# 03_iMX_8X_PMIC.net
KiCad netlist of a schematic drawn in Altium Designer
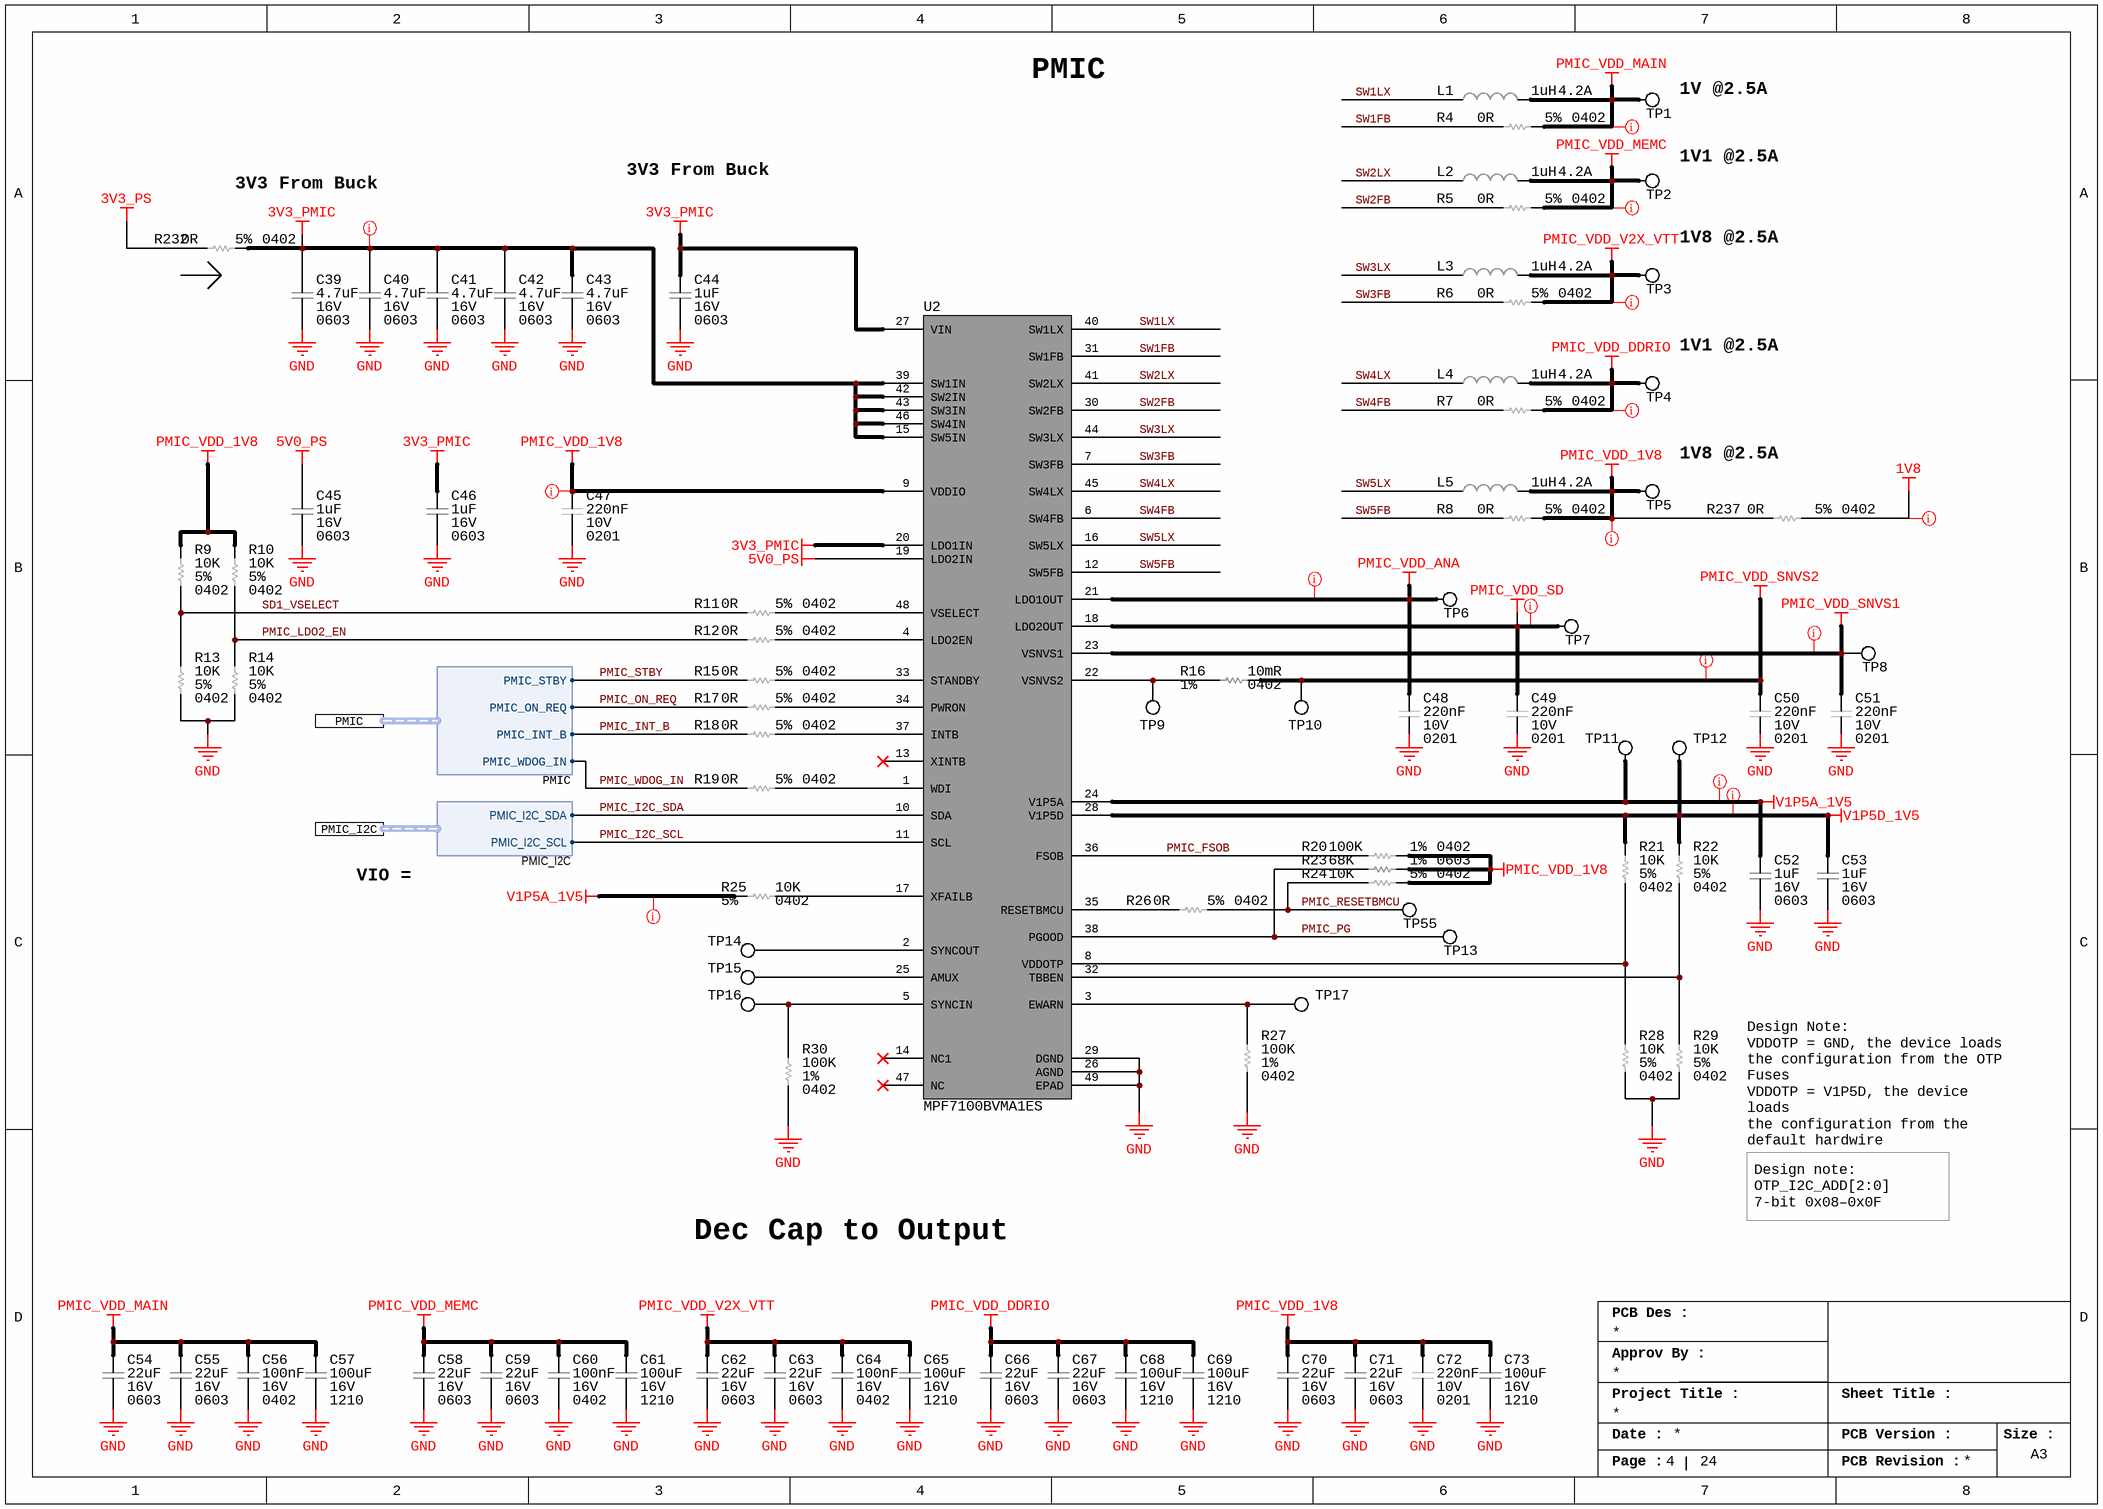
[diagram p0: 03_iMX 8X_PMIC.SchDoc]

(export (version "E")
  (design (tool "Eeschema 10.0.6"))
  (components
    (comp (ref "C39")
      (value "CL10A475KO8NNNC")
      (footprint "CAP_0603_CAPC1608X08N")
      (description "CAP CER 4.7UF 16V X5R 0603")
      (fields
        (field (name "MANUFACTURER") "Samsung")
        (field (name "TOLERANCE") "10%")
        (field (name "VOLTAGE") "16V")
        (field (name "CAPACITANCE") "4.7uF")
        (field (name "CASE/PACKAGE") "0603")
      )
      (libsource (lib "Electronic Devices_LIB") (part "CAP_4.7UF_16V_X5R_0603"))
    )
    (comp (ref "C40")
      (value "CL10A475KO8NNNC")
      (footprint "CAP_0603_CAPC1608X08N")
      (description "CAP CER 4.7UF 16V X5R 0603")
      (fields
        (field (name "MANUFACTURER") "Samsung")
        (field (name "TOLERANCE") "10%")
        (field (name "VOLTAGE") "16V")
        (field (name "CAPACITANCE") "4.7uF")
        (field (name "CASE/PACKAGE") "0603")
      )
      (libsource (lib "Electronic Devices_LIB") (part "CAP_4.7UF_16V_X5R_0603"))
    )
    (comp (ref "C41")
      (value "CL10A475KO8NNNC")
      (footprint "CAP_0603_CAPC1608X08N")
      (description "CAP CER 4.7UF 16V X5R 0603")
      (fields
        (field (name "MANUFACTURER") "Samsung")
        (field (name "TOLERANCE") "10%")
        (field (name "VOLTAGE") "16V")
        (field (name "CAPACITANCE") "4.7uF")
        (field (name "CASE/PACKAGE") "0603")
      )
      (libsource (lib "Electronic Devices_LIB") (part "CAP_4.7UF_16V_X5R_0603"))
    )
    (comp (ref "C42")
      (value "CL10A475KO8NNNC")
      (footprint "CAP_0603_CAPC1608X08N")
      (description "CAP CER 4.7UF 16V X5R 0603")
      (fields
        (field (name "MANUFACTURER") "Samsung")
        (field (name "TOLERANCE") "10%")
        (field (name "VOLTAGE") "16V")
        (field (name "CAPACITANCE") "4.7uF")
        (field (name "CASE/PACKAGE") "0603")
      )
      (libsource (lib "Electronic Devices_LIB") (part "CAP_4.7UF_16V_X5R_0603"))
    )
    (comp (ref "C43")
      (value "CL10A475KO8NNNC")
      (footprint "CAP_0603_CAPC1608X08N")
      (description "CAP CER 4.7UF 16V X5R 0603")
      (fields
        (field (name "MANUFACTURER") "Samsung")
        (field (name "TOLERANCE") "10%")
        (field (name "VOLTAGE") "16V")
        (field (name "CAPACITANCE") "4.7uF")
        (field (name "CASE/PACKAGE") "0603")
      )
      (libsource (lib "Electronic Devices_LIB") (part "CAP_4.7UF_16V_X5R_0603"))
    )
    (comp (ref "C44")
      (value "CL10A105KO8NNNC")
      (footprint "CAP_0603_CAPC1608X08N")
      (description "CAP CER 1UF 16V X5R 0603")
      (fields
        (field (name "MANUFACTURER") "Samsung")
        (field (name "TOLERANCE") "10%")
        (field (name "VOLTAGE RATING") "16V")
        (field (name "CAPACITANCE") "1uF")
        (field (name "CASE/PACKAGE") "0603")
      )
      (libsource (lib "Electronic Devices_LIB") (part "CAP_1UF_16V_X5R_0603"))
    )
    (comp (ref "C45")
      (value "CL10A105KO8NNNC")
      (footprint "CAP_0603_CAPC1608X08N")
      (description "CAP CER 1UF 16V X5R 0603")
      (fields
        (field (name "MANUFACTURER") "Samsung")
        (field (name "TOLERANCE") "10%")
        (field (name "VOLTAGE RATING") "16V")
        (field (name "CAPACITANCE") "1uF")
        (field (name "CASE/PACKAGE") "0603")
      )
      (libsource (lib "Electronic Devices_LIB") (part "CAP_1UF_16V_X5R_0603"))
    )
    (comp (ref "C46")
      (value "CL10A105KO8NNNC")
      (footprint "CAP_0603_CAPC1608X08N")
      (description "CAP CER 1UF 16V X5R 0603")
      (fields
        (field (name "MANUFACTURER") "Samsung")
        (field (name "TOLERANCE") "10%")
        (field (name "VOLTAGE RATING") "16V")
        (field (name "CAPACITANCE") "1uF")
        (field (name "CASE/PACKAGE") "0603")
      )
      (libsource (lib "Electronic Devices_LIB") (part "CAP_1UF_16V_X5R_0603"))
    )
    (comp (ref "C47")
      (value "LMK063BJ224MP-F")
      (footprint "CAP_0201_CAPC0603X03N")
      (description "Multilayer Ceramic Capacitors (High dielectric type), 10V, 0.22 uF, ± 20 %, 0201, X5R, RoHS")
      (fields
        (field (name "MANUFACTURER") "Taiyo Yuden")
        (field (name "TOLERANCE") "20%")
        (field (name "VOLTAGE RATING (DC)") "10V")
        (field (name "CAPACITANCE") "220nF")
        (field (name "CASE/PACKAGE") "0201")
      )
      (libsource (lib "Electronic Devices_LIB") (part "CAP_0.22UF_10V_X5R_0201"))
    )
    (comp (ref "C48")
      (value "LMK063BJ224MP-F")
      (footprint "CAP_0201_CAPC0603X03N")
      (description "Multilayer Ceramic Capacitors (High dielectric type), 10V, 0.22 uF, ± 20 %, 0201, X5R, RoHS")
      (fields
        (field (name "MANUFACTURER") "Taiyo Yuden")
        (field (name "TOLERANCE") "20%")
        (field (name "VOLTAGE RATING (DC)") "10V")
        (field (name "CAPACITANCE") "220nF")
        (field (name "CASE/PACKAGE") "0201")
      )
      (libsource (lib "Electronic Devices_LIB") (part "CAP_0.22UF_10V_X5R_0201"))
    )
    (comp (ref "C49")
      (value "LMK063BJ224MP-F")
      (footprint "CAP_0201_CAPC0603X03N")
      (description "Multilayer Ceramic Capacitors (High dielectric type), 10V, 0.22 uF, ± 20 %, 0201, X5R, RoHS")
      (fields
        (field (name "MANUFACTURER") "Taiyo Yuden")
        (field (name "TOLERANCE") "20%")
        (field (name "VOLTAGE RATING (DC)") "10V")
        (field (name "CAPACITANCE") "220nF")
        (field (name "CASE/PACKAGE") "0201")
      )
      (libsource (lib "Electronic Devices_LIB") (part "CAP_0.22UF_10V_X5R_0201"))
    )
    (comp (ref "C50")
      (value "LMK063BJ224MP-F")
      (footprint "CAP_0201_CAPC0603X03N")
      (description "Multilayer Ceramic Capacitors (High dielectric type), 10V, 0.22 uF, ± 20 %, 0201, X5R, RoHS")
      (fields
        (field (name "MANUFACTURER") "Taiyo Yuden")
        (field (name "TOLERANCE") "20%")
        (field (name "VOLTAGE RATING (DC)") "10V")
        (field (name "CAPACITANCE") "220nF")
        (field (name "CASE/PACKAGE") "0201")
      )
      (libsource (lib "Electronic Devices_LIB") (part "CAP_0.22UF_10V_X5R_0201"))
    )
    (comp (ref "C51")
      (value "LMK063BJ224MP-F")
      (footprint "CAP_0201_CAPC0603X03N")
      (description "Multilayer Ceramic Capacitors (High dielectric type), 10V, 0.22 uF, ± 20 %, 0201, X5R, RoHS")
      (fields
        (field (name "MANUFACTURER") "Taiyo Yuden")
        (field (name "TOLERANCE") "20%")
        (field (name "VOLTAGE RATING (DC)") "10V")
        (field (name "CAPACITANCE") "220nF")
        (field (name "CASE/PACKAGE") "0201")
      )
      (libsource (lib "Electronic Devices_LIB") (part "CAP_0.22UF_10V_X5R_0201"))
    )
    (comp (ref "C52")
      (value "CL10A105KO8NNNC")
      (footprint "CAP_0603_CAPC1608X08N")
      (description "CAP CER 1UF 16V X5R 0603")
      (fields
        (field (name "MANUFACTURER") "Samsung")
        (field (name "TOLERANCE") "10%")
        (field (name "VOLTAGE RATING") "16V")
        (field (name "CAPACITANCE") "1uF")
        (field (name "CASE/PACKAGE") "0603")
      )
      (libsource (lib "Electronic Devices_LIB") (part "CAP_1UF_16V_X5R_0603"))
    )
    (comp (ref "C53")
      (value "CL10A105KO8NNNC")
      (footprint "CAP_0603_CAPC1608X08N")
      (description "CAP CER 1UF 16V X5R 0603")
      (fields
        (field (name "MANUFACTURER") "Samsung")
        (field (name "TOLERANCE") "10%")
        (field (name "VOLTAGE RATING") "16V")
        (field (name "CAPACITANCE") "1uF")
        (field (name "CASE/PACKAGE") "0603")
      )
      (libsource (lib "Electronic Devices_LIB") (part "CAP_1UF_16V_X5R_0603"))
    )
    (comp (ref "C54")
      (value "CL10A226MO7JZNC")
      (footprint "CAP_0603_CAPC1608X08N")
      (description "Cap Ceramic 22uF 16V X5R 20% Pad SMD 0603 85C T/R")
      (fields
        (field (name "MANUFACTURER") "Samsung")
        (field (name "TOLERANCE") "20%")
        (field (name "CAPACITANCE") "22uF")
        (field (name "VOLTAGE RATING") "16V")
        (field (name "CASE/PACKAGE") "0603")
      )
      (libsource (lib "Electronic Devices_LIB") (part "CAP_22UF_16V_X5R_0603"))
    )
    (comp (ref "C55")
      (value "CL10A226MO7JZNC")
      (footprint "CAP_0603_CAPC1608X08N")
      (description "Cap Ceramic 22uF 16V X5R 20% Pad SMD 0603 85C T/R")
      (fields
        (field (name "MANUFACTURER") "Samsung")
        (field (name "TOLERANCE") "20%")
        (field (name "CAPACITANCE") "22uF")
        (field (name "VOLTAGE RATING") "16V")
        (field (name "CASE/PACKAGE") "0603")
      )
      (libsource (lib "Electronic Devices_LIB") (part "CAP_22UF_16V_X5R_0603"))
    )
    (comp (ref "C56")
      (value "CL05B104KO5NNNC")
      (footprint "CAP_0402_CAPC1005X05N")
      (description "Multilayer Ceramic Capacitor, 0.1 uF, 16 V, ± 10%, X7R, 0402 [1005 Metric]")
      (fields
        (field (name "MANUFACTURER") "Samsung")
        (field (name "TOLERANCE") "10%")
        (field (name "VOLTAGE RATING") "16V")
        (field (name "CAPACITANCE") "100nF")
        (field (name "CASE/PACKAGE") "0402")
      )
      (libsource (lib "Electronic Devices_LIB") (part "CAP_100NF_16V_X7R_0402"))
    )
    (comp (ref "C57")
      (value "EMK325ABJ107MM-T")
      (footprint "CAP_1210_CAPC3225X270N")
      (description "Multilayer Ceramic Capacitor, 100 uF, 16 V, ± 20%, X5R, 1210 [3225 Metric]")
      (fields
        (field (name "MANUFACTURER") "Taiyo Yuden")
        (field (name "TOLERANCE") "20%")
        (field (name "VOLTAGE RATING") "16V")
        (field (name "CAPACITANCE") "100uF")
        (field (name "CASE/PACKAGE") "1210")
      )
      (libsource (lib "Electronic Devices_LIB") (part "CAP_100UF_16V_X5R_1210"))
    )
    (comp (ref "C58")
      (value "CL10A226MO7JZNC")
      (footprint "CAP_0603_CAPC1608X08N")
      (description "Cap Ceramic 22uF 16V X5R 20% Pad SMD 0603 85C T/R")
      (fields
        (field (name "MANUFACTURER") "Samsung")
        (field (name "TOLERANCE") "20%")
        (field (name "CAPACITANCE") "22uF")
        (field (name "VOLTAGE RATING") "16V")
        (field (name "CASE/PACKAGE") "0603")
      )
      (libsource (lib "Electronic Devices_LIB") (part "CAP_22UF_16V_X5R_0603"))
    )
    (comp (ref "C59")
      (value "CL10A226MO7JZNC")
      (footprint "CAP_0603_CAPC1608X08N")
      (description "Cap Ceramic 22uF 16V X5R 20% Pad SMD 0603 85C T/R")
      (fields
        (field (name "MANUFACTURER") "Samsung")
        (field (name "TOLERANCE") "20%")
        (field (name "CAPACITANCE") "22uF")
        (field (name "VOLTAGE RATING") "16V")
        (field (name "CASE/PACKAGE") "0603")
      )
      (libsource (lib "Electronic Devices_LIB") (part "CAP_22UF_16V_X5R_0603"))
    )
    (comp (ref "C60")
      (value "CL05B104KO5NNNC")
      (footprint "CAP_0402_CAPC1005X05N")
      (description "Multilayer Ceramic Capacitor, 0.1 uF, 16 V, ± 10%, X7R, 0402 [1005 Metric]")
      (fields
        (field (name "MANUFACTURER") "Samsung")
        (field (name "TOLERANCE") "10%")
        (field (name "VOLTAGE RATING") "16V")
        (field (name "CAPACITANCE") "100nF")
        (field (name "CASE/PACKAGE") "0402")
      )
      (libsource (lib "Electronic Devices_LIB") (part "CAP_100NF_16V_X7R_0402"))
    )
    (comp (ref "C61")
      (value "EMK325ABJ107MM-T")
      (footprint "CAP_1210_CAPC3225X270N")
      (description "Multilayer Ceramic Capacitor, 100 uF, 16 V, ± 20%, X5R, 1210 [3225 Metric]")
      (fields
        (field (name "MANUFACTURER") "Taiyo Yuden")
        (field (name "TOLERANCE") "20%")
        (field (name "VOLTAGE RATING") "16V")
        (field (name "CAPACITANCE") "100uF")
        (field (name "CASE/PACKAGE") "1210")
      )
      (libsource (lib "Electronic Devices_LIB") (part "CAP_100UF_16V_X5R_1210"))
    )
    (comp (ref "C62")
      (value "CL10A226MO7JZNC")
      (footprint "CAP_0603_CAPC1608X08N")
      (description "Cap Ceramic 22uF 16V X5R 20% Pad SMD 0603 85C T/R")
      (fields
        (field (name "MANUFACTURER") "Samsung")
        (field (name "TOLERANCE") "20%")
        (field (name "CAPACITANCE") "22uF")
        (field (name "VOLTAGE RATING") "16V")
        (field (name "CASE/PACKAGE") "0603")
      )
      (libsource (lib "Electronic Devices_LIB") (part "CAP_22UF_16V_X5R_0603"))
    )
    (comp (ref "C63")
      (value "CL10A226MO7JZNC")
      (footprint "CAP_0603_CAPC1608X08N")
      (description "Cap Ceramic 22uF 16V X5R 20% Pad SMD 0603 85C T/R")
      (fields
        (field (name "MANUFACTURER") "Samsung")
        (field (name "TOLERANCE") "20%")
        (field (name "CAPACITANCE") "22uF")
        (field (name "VOLTAGE RATING") "16V")
        (field (name "CASE/PACKAGE") "0603")
      )
      (libsource (lib "Electronic Devices_LIB") (part "CAP_22UF_16V_X5R_0603"))
    )
    (comp (ref "C64")
      (value "CL05B104KO5NNNC")
      (footprint "CAP_0402_CAPC1005X05N")
      (description "Multilayer Ceramic Capacitor, 0.1 uF, 16 V, ± 10%, X7R, 0402 [1005 Metric]")
      (fields
        (field (name "MANUFACTURER") "Samsung")
        (field (name "TOLERANCE") "10%")
        (field (name "VOLTAGE RATING") "16V")
        (field (name "CAPACITANCE") "100nF")
        (field (name "CASE/PACKAGE") "0402")
      )
      (libsource (lib "Electronic Devices_LIB") (part "CAP_100NF_16V_X7R_0402"))
    )
    (comp (ref "C65")
      (value "EMK325ABJ107MM-T")
      (footprint "CAP_1210_CAPC3225X270N")
      (description "Multilayer Ceramic Capacitor, 100 uF, 16 V, ± 20%, X5R, 1210 [3225 Metric]")
      (fields
        (field (name "MANUFACTURER") "Taiyo Yuden")
        (field (name "TOLERANCE") "20%")
        (field (name "VOLTAGE RATING") "16V")
        (field (name "CAPACITANCE") "100uF")
        (field (name "CASE/PACKAGE") "1210")
      )
      (libsource (lib "Electronic Devices_LIB") (part "CAP_100UF_16V_X5R_1210"))
    )
    (comp (ref "C66")
      (value "CL10A226MO7JZNC")
      (footprint "CAP_0603_CAPC1608X08N")
      (description "Cap Ceramic 22uF 16V X5R 20% Pad SMD 0603 85C T/R")
      (fields
        (field (name "MANUFACTURER") "Samsung")
        (field (name "TOLERANCE") "20%")
        (field (name "CAPACITANCE") "22uF")
        (field (name "VOLTAGE RATING") "16V")
        (field (name "CASE/PACKAGE") "0603")
      )
      (libsource (lib "Electronic Devices_LIB") (part "CAP_22UF_16V_X5R_0603"))
    )
    (comp (ref "C67")
      (value "CL10A226MO7JZNC")
      (footprint "CAP_0603_CAPC1608X08N")
      (description "Cap Ceramic 22uF 16V X5R 20% Pad SMD 0603 85C T/R")
      (fields
        (field (name "MANUFACTURER") "Samsung")
        (field (name "TOLERANCE") "20%")
        (field (name "CAPACITANCE") "22uF")
        (field (name "VOLTAGE RATING") "16V")
        (field (name "CASE/PACKAGE") "0603")
      )
      (libsource (lib "Electronic Devices_LIB") (part "CAP_22UF_16V_X5R_0603"))
    )
    (comp (ref "C68")
      (value "EMK325ABJ107MM-T")
      (footprint "CAP_1210_CAPC3225X270N")
      (description "Multilayer Ceramic Capacitor, 100 uF, 16 V, ± 20%, X5R, 1210 [3225 Metric]")
      (fields
        (field (name "MANUFACTURER") "Taiyo Yuden")
        (field (name "TOLERANCE") "20%")
        (field (name "VOLTAGE RATING") "16V")
        (field (name "CAPACITANCE") "100uF")
        (field (name "CASE/PACKAGE") "1210")
      )
      (libsource (lib "Electronic Devices_LIB") (part "CAP_100UF_16V_X5R_1210"))
    )
    (comp (ref "C69")
      (value "EMK325ABJ107MM-T")
      (footprint "CAP_1210_CAPC3225X270N")
      (description "Multilayer Ceramic Capacitor, 100 uF, 16 V, ± 20%, X5R, 1210 [3225 Metric]")
      (fields
        (field (name "MANUFACTURER") "Taiyo Yuden")
        (field (name "TOLERANCE") "20%")
        (field (name "VOLTAGE RATING") "16V")
        (field (name "CAPACITANCE") "100uF")
        (field (name "CASE/PACKAGE") "1210")
      )
      (libsource (lib "Electronic Devices_LIB") (part "CAP_100UF_16V_X5R_1210"))
    )
    (comp (ref "C70")
      (value "CL10A226MO7JZNC")
      (footprint "CAP_0603_CAPC1608X08N")
      (description "Cap Ceramic 22uF 16V X5R 20% Pad SMD 0603 85C T/R")
      (fields
        (field (name "MANUFACTURER") "Samsung")
        (field (name "TOLERANCE") "20%")
        (field (name "CAPACITANCE") "22uF")
        (field (name "VOLTAGE RATING") "16V")
        (field (name "CASE/PACKAGE") "0603")
      )
      (libsource (lib "Electronic Devices_LIB") (part "CAP_22UF_16V_X5R_0603"))
    )
    (comp (ref "C71")
      (value "CL10A226MO7JZNC")
      (footprint "CAP_0603_CAPC1608X08N")
      (description "Cap Ceramic 22uF 16V X5R 20% Pad SMD 0603 85C T/R")
      (fields
        (field (name "MANUFACTURER") "Samsung")
        (field (name "TOLERANCE") "20%")
        (field (name "CAPACITANCE") "22uF")
        (field (name "VOLTAGE RATING") "16V")
        (field (name "CASE/PACKAGE") "0603")
      )
      (libsource (lib "Electronic Devices_LIB") (part "CAP_22UF_16V_X5R_0603"))
    )
    (comp (ref "C72")
      (value "LMK063BJ224MP-F")
      (footprint "CAP_0201_CAPC0603X03N")
      (description "Multilayer Ceramic Capacitors (High dielectric type), 10V, 0.22 uF, ± 20 %, 0201, X5R, RoHS")
      (fields
        (field (name "MANUFACTURER") "Taiyo Yuden")
        (field (name "TOLERANCE") "20%")
        (field (name "VOLTAGE RATING (DC)") "10V")
        (field (name "CAPACITANCE") "220nF")
        (field (name "CASE/PACKAGE") "0201")
      )
      (libsource (lib "Electronic Devices_LIB") (part "CAP_0.22UF_10V_X5R_0201"))
    )
    (comp (ref "C73")
      (value "EMK325ABJ107MM-T")
      (footprint "CAP_1210_CAPC3225X270N")
      (description "Multilayer Ceramic Capacitor, 100 uF, 16 V, ± 20%, X5R, 1210 [3225 Metric]")
      (fields
        (field (name "MANUFACTURER") "Taiyo Yuden")
        (field (name "TOLERANCE") "20%")
        (field (name "VOLTAGE RATING") "16V")
        (field (name "CAPACITANCE") "100uF")
        (field (name "CASE/PACKAGE") "1210")
      )
      (libsource (lib "Electronic Devices_LIB") (part "CAP_100UF_16V_X5R_1210"))
    )
    (comp (ref "L1")
      (value "TFM252012ALMA1R0MTAA")
      (footprint "INDC2520X120N")
      (description "Inductor Power Shielded Thin Film 1uH 20% 1MHz Metal 3.7A 0.042Ohm DCR 1008 Automotive T/R")
      (fields
        (field (name "MANUFACTURER") "TDK")
        (field (name "TOLERANCE") "20%")
        (field (name "SATURATION CURRENT") "4.2A")
        (field (name "INDUCTANCE") "1uH")
      )
      (libsource (lib "Electronic Devices_LIB") (part "IND_1uH_3.7A_TFM252012ALMA1R0MTAA"))
    )
    (comp (ref "L2")
      (value "TFM252012ALMA1R0MTAA")
      (footprint "INDC2520X120N")
      (description "Inductor Power Shielded Thin Film 1uH 20% 1MHz Metal 3.7A 0.042Ohm DCR 1008 Automotive T/R")
      (fields
        (field (name "MANUFACTURER") "TDK")
        (field (name "TOLERANCE") "20%")
        (field (name "SATURATION CURRENT") "4.2A")
        (field (name "INDUCTANCE") "1uH")
      )
      (libsource (lib "Electronic Devices_LIB") (part "IND_1uH_3.7A_TFM252012ALMA1R0MTAA"))
    )
    (comp (ref "L3")
      (value "TFM252012ALMA1R0MTAA")
      (footprint "INDC2520X120N")
      (description "Inductor Power Shielded Thin Film 1uH 20% 1MHz Metal 3.7A 0.042Ohm DCR 1008 Automotive T/R")
      (fields
        (field (name "MANUFACTURER") "TDK")
        (field (name "TOLERANCE") "20%")
        (field (name "SATURATION CURRENT") "4.2A")
        (field (name "INDUCTANCE") "1uH")
      )
      (libsource (lib "Electronic Devices_LIB") (part "IND_1uH_3.7A_TFM252012ALMA1R0MTAA"))
    )
    (comp (ref "L4")
      (value "TFM252012ALMA1R0MTAA")
      (footprint "INDC2520X120N")
      (description "Inductor Power Shielded Thin Film 1uH 20% 1MHz Metal 3.7A 0.042Ohm DCR 1008 Automotive T/R")
      (fields
        (field (name "MANUFACTURER") "TDK")
        (field (name "TOLERANCE") "20%")
        (field (name "SATURATION CURRENT") "4.2A")
        (field (name "INDUCTANCE") "1uH")
      )
      (libsource (lib "Electronic Devices_LIB") (part "IND_1uH_3.7A_TFM252012ALMA1R0MTAA"))
    )
    (comp (ref "L5")
      (value "TFM252012ALMA1R0MTAA")
      (footprint "INDC2520X120N")
      (description "Inductor Power Shielded Thin Film 1uH 20% 1MHz Metal 3.7A 0.042Ohm DCR 1008 Automotive T/R")
      (fields
        (field (name "MANUFACTURER") "TDK")
        (field (name "TOLERANCE") "20%")
        (field (name "SATURATION CURRENT") "4.2A")
        (field (name "INDUCTANCE") "1uH")
      )
      (libsource (lib "Electronic Devices_LIB") (part "IND_1uH_3.7A_TFM252012ALMA1R0MTAA"))
    )
    (comp (ref "R4")
      (value "ERJ-2GE0R00X")
      (footprint "RES_0402_RESC1005X04N")
      (description "SMD Chip Resistor, Jumper, 0 ohm, 100 mW, 0402 [1005 Metric], Thick Film, General Purpose")
      (fields
        (field (name "MANUFACTURER") "Panasonic")
        (field (name "CASE CODE (IMPERIAL)") "0402")
        (field (name "TOLERANCE") "5%")
        (field (name "RESISTANCE") "0R")
      )
      (libsource (lib "Electronic Devices_LIB") (part "RES_0R_5%_100mW_0402"))
    )
    (comp (ref "R5")
      (value "ERJ-2GE0R00X")
      (footprint "RES_0402_RESC1005X04N")
      (description "SMD Chip Resistor, Jumper, 0 ohm, 100 mW, 0402 [1005 Metric], Thick Film, General Purpose")
      (fields
        (field (name "MANUFACTURER") "Panasonic")
        (field (name "CASE CODE (IMPERIAL)") "0402")
        (field (name "TOLERANCE") "5%")
        (field (name "RESISTANCE") "0R")
      )
      (libsource (lib "Electronic Devices_LIB") (part "RES_0R_5%_100mW_0402"))
    )
    (comp (ref "R6")
      (value "ERJ-2GE0R00X")
      (footprint "RES_0402_RESC1005X04N")
      (description "SMD Chip Resistor, Jumper, 0 ohm, 100 mW, 0402 [1005 Metric], Thick Film, General Purpose")
      (fields
        (field (name "MANUFACTURER") "Panasonic")
        (field (name "CASE CODE (IMPERIAL)") "0402")
        (field (name "TOLERANCE") "5%")
        (field (name "RESISTANCE") "0R")
      )
      (libsource (lib "Electronic Devices_LIB") (part "RES_0R_5%_100mW_0402"))
    )
    (comp (ref "R7")
      (value "ERJ-2GE0R00X")
      (footprint "RES_0402_RESC1005X04N")
      (description "SMD Chip Resistor, Jumper, 0 ohm, 100 mW, 0402 [1005 Metric], Thick Film, General Purpose")
      (fields
        (field (name "MANUFACTURER") "Panasonic")
        (field (name "CASE CODE (IMPERIAL)") "0402")
        (field (name "TOLERANCE") "5%")
        (field (name "RESISTANCE") "0R")
      )
      (libsource (lib "Electronic Devices_LIB") (part "RES_0R_5%_100mW_0402"))
    )
    (comp (ref "R8")
      (value "ERJ-2GE0R00X")
      (footprint "RES_0402_RESC1005X04N")
      (description "SMD Chip Resistor, Jumper, 0 ohm, 100 mW, 0402 [1005 Metric], Thick Film, General Purpose")
      (fields
        (field (name "MANUFACTURER") "Panasonic")
        (field (name "CASE CODE (IMPERIAL)") "0402")
        (field (name "TOLERANCE") "5%")
        (field (name "RESISTANCE") "0R")
      )
      (libsource (lib "Electronic Devices_LIB") (part "RES_0R_5%_100mW_0402"))
    )
    (comp (ref "R9")
      (value "ERJ-2GEJ103X")
      (footprint "RES_0402_RESC1005X04N")
      (description "Res Thick Film 0402 10K Ohm 5% 1/10W ±200ppm/°C Molded SMD Punched Carrier T/R")
      (fields
        (field (name "MANUFACTURER") "Panasonic")
        (field (name "TOLERANCE") "5%")
        (field (name "RESISTANCE") "10K")
        (field (name "CASE/PACKAGE") "0402")
      )
      (libsource (lib "Electronic Devices_LIB") (part "RES_10K_5%_100mW_0402"))
    )
    (comp (ref "R10")
      (value "ERJ-2GEJ103X")
      (footprint "RES_0402_RESC1005X04N")
      (description "Res Thick Film 0402 10K Ohm 5% 1/10W ±200ppm/°C Molded SMD Punched Carrier T/R")
      (fields
        (field (name "MANUFACTURER") "Panasonic")
        (field (name "TOLERANCE") "5%")
        (field (name "RESISTANCE") "10K")
        (field (name "CASE/PACKAGE") "0402")
      )
      (libsource (lib "Electronic Devices_LIB") (part "RES_10K_5%_100mW_0402"))
    )
    (comp (ref "R11")
      (value "ERJ-2GE0R00X")
      (footprint "RES_0402_RESC1005X04N")
      (description "SMD Chip Resistor, Jumper, 0 ohm, 100 mW, 0402 [1005 Metric], Thick Film, General Purpose")
      (fields
        (field (name "MANUFACTURER") "Panasonic")
        (field (name "CASE CODE (IMPERIAL)") "0402")
        (field (name "TOLERANCE") "5%")
        (field (name "RESISTANCE") "0R")
      )
      (libsource (lib "Electronic Devices_LIB") (part "RES_0R_5%_100mW_0402"))
    )
    (comp (ref "R12")
      (value "ERJ-2GE0R00X")
      (footprint "RES_0402_RESC1005X04N")
      (description "SMD Chip Resistor, Jumper, 0 ohm, 100 mW, 0402 [1005 Metric], Thick Film, General Purpose")
      (fields
        (field (name "MANUFACTURER") "Panasonic")
        (field (name "CASE CODE (IMPERIAL)") "0402")
        (field (name "TOLERANCE") "5%")
        (field (name "RESISTANCE") "0R")
      )
      (libsource (lib "Electronic Devices_LIB") (part "RES_0R_5%_100mW_0402"))
    )
    (comp (ref "R13")
      (value "ERJ-2GEJ103X")
      (footprint "RES_0402_RESC1005X04N")
      (description "Res Thick Film 0402 10K Ohm 5% 1/10W ±200ppm/°C Molded SMD Punched Carrier T/R")
      (fields
        (field (name "MANUFACTURER") "Panasonic")
        (field (name "TOLERANCE") "5%")
        (field (name "RESISTANCE") "10K")
        (field (name "CASE/PACKAGE") "0402")
      )
      (libsource (lib "Electronic Devices_LIB") (part "RES_10K_5%_100mW_0402"))
    )
    (comp (ref "R14")
      (value "ERJ-2GEJ103X")
      (footprint "RES_0402_RESC1005X04N")
      (description "Res Thick Film 0402 10K Ohm 5% 1/10W ±200ppm/°C Molded SMD Punched Carrier T/R")
      (fields
        (field (name "MANUFACTURER") "Panasonic")
        (field (name "TOLERANCE") "5%")
        (field (name "RESISTANCE") "10K")
        (field (name "CASE/PACKAGE") "0402")
      )
      (libsource (lib "Electronic Devices_LIB") (part "RES_10K_5%_100mW_0402"))
    )
    (comp (ref "R15")
      (value "ERJ-2GE0R00X")
      (footprint "RES_0402_RESC1005X04N")
      (description "SMD Chip Resistor, Jumper, 0 ohm, 100 mW, 0402 [1005 Metric], Thick Film, General Purpose")
      (fields
        (field (name "MANUFACTURER") "Panasonic")
        (field (name "CASE CODE (IMPERIAL)") "0402")
        (field (name "TOLERANCE") "5%")
        (field (name "RESISTANCE") "0R")
      )
      (libsource (lib "Electronic Devices_LIB") (part "RES_0R_5%_100mW_0402"))
    )
    (comp (ref "R16")
      (value "ERJ-2LWFR010X")
      (footprint "RES_0603_RESC1608X04N")
      (description "Res Current Sense Thick Film 0402 0.01 Ohm 1% 1/5W 0ppm/°C to 500ppm/°C Molded T/R")
      (fields
        (field (name "MANUFACTURER") "Panasonic")
        (field (name "TOLERANCE") "1%")
        (field (name "RESISTANCE") "10mR")
        (field (name "CASE/PACKAGE") "0402")
      )
      (libsource (lib "Electronic Devices_LIB") (part "RES_10mR_1%_0.05W_0402"))
    )
    (comp (ref "R17")
      (value "ERJ-2GE0R00X")
      (footprint "RES_0402_RESC1005X04N")
      (description "SMD Chip Resistor, Jumper, 0 ohm, 100 mW, 0402 [1005 Metric], Thick Film, General Purpose")
      (fields
        (field (name "MANUFACTURER") "Panasonic")
        (field (name "CASE CODE (IMPERIAL)") "0402")
        (field (name "TOLERANCE") "5%")
        (field (name "RESISTANCE") "0R")
      )
      (libsource (lib "Electronic Devices_LIB") (part "RES_0R_5%_100mW_0402"))
    )
    (comp (ref "R18")
      (value "ERJ-2GE0R00X")
      (footprint "RES_0402_RESC1005X04N")
      (description "SMD Chip Resistor, Jumper, 0 ohm, 100 mW, 0402 [1005 Metric], Thick Film, General Purpose")
      (fields
        (field (name "MANUFACTURER") "Panasonic")
        (field (name "CASE CODE (IMPERIAL)") "0402")
        (field (name "TOLERANCE") "5%")
        (field (name "RESISTANCE") "0R")
      )
      (libsource (lib "Electronic Devices_LIB") (part "RES_0R_5%_100mW_0402"))
    )
    (comp (ref "R19")
      (value "ERJ-2GE0R00X")
      (footprint "RES_0402_RESC1005X04N")
      (description "SMD Chip Resistor, Jumper, 0 ohm, 100 mW, 0402 [1005 Metric], Thick Film, General Purpose")
      (fields
        (field (name "MANUFACTURER") "Panasonic")
        (field (name "CASE CODE (IMPERIAL)") "0402")
        (field (name "TOLERANCE") "5%")
        (field (name "RESISTANCE") "0R")
      )
      (libsource (lib "Electronic Devices_LIB") (part "RES_0R_5%_100mW_0402"))
    )
    (comp (ref "R20")
      (value "RC0402FR-07100KL")
      (footprint "RES_0402_RESC1005X04N")
      (description "SMD Chip Resistor, 100 kOhm, ± 1%, 63 mW, 0402 [1005 Metric], Thick Film, General Purpose")
      (fields
        (field (name "MANUFACTURER") "Yageo")
        (field (name "RESISTANCE") "100K")
        (field (name "TOLERANCE") "1%")
        (field (name "CASE/PACKAGE") "0402")
      )
      (libsource (lib "Electronic Devices_LIB") (part "RES_100K_1%_100mW_0402"))
    )
    (comp (ref "R21")
      (value "ERJ-2GEJ103X")
      (footprint "RES_0402_RESC1005X04N")
      (description "Res Thick Film 0402 10K Ohm 5% 1/10W ±200ppm/°C Molded SMD Punched Carrier T/R")
      (fields
        (field (name "MANUFACTURER") "Panasonic")
        (field (name "TOLERANCE") "5%")
        (field (name "RESISTANCE") "10K")
        (field (name "CASE/PACKAGE") "0402")
      )
      (libsource (lib "Electronic Devices_LIB") (part "RES_10K_5%_100mW_0402"))
    )
    (comp (ref "R22")
      (value "ERJ-2GEJ103X")
      (footprint "RES_0402_RESC1005X04N")
      (description "Res Thick Film 0402 10K Ohm 5% 1/10W ±200ppm/°C Molded SMD Punched Carrier T/R")
      (fields
        (field (name "MANUFACTURER") "Panasonic")
        (field (name "TOLERANCE") "5%")
        (field (name "RESISTANCE") "10K")
        (field (name "CASE/PACKAGE") "0402")
      )
      (libsource (lib "Electronic Devices_LIB") (part "RES_10K_5%_100mW_0402"))
    )
    (comp (ref "R23")
      (value "RC0603FR-0768KL")
      (footprint "RES_0603_RESC1608X04N")
      (description "SMD Chip Resistor, 68 kOhm, ± 1%, 100 mW, 0603 [1608 Metric], Thick Film, General Purpose")
      (fields
        (field (name "MANUFACTURER") "Yageo")
        (field (name "TOLERANCE") "1%")
        (field (name "RESISTANCE") "68K")
        (field (name "CASE/PACKAGE") "0603")
      )
      (libsource (lib "Electronic Devices_LIB") (part "RES_68K_1%_100mW_0603"))
    )
    (comp (ref "R24")
      (value "ERJ-2GEJ103X")
      (footprint "RES_0402_RESC1005X04N")
      (description "Res Thick Film 0402 10K Ohm 5% 1/10W ±200ppm/°C Molded SMD Punched Carrier T/R")
      (fields
        (field (name "MANUFACTURER") "Panasonic")
        (field (name "TOLERANCE") "5%")
        (field (name "RESISTANCE") "10K")
        (field (name "CASE/PACKAGE") "0402")
      )
      (libsource (lib "Electronic Devices_LIB") (part "RES_10K_5%_100mW_0402"))
    )
    (comp (ref "R25")
      (value "ERJ-2GEJ103X")
      (footprint "RES_0402_RESC1005X04N")
      (description "Res Thick Film 0402 10K Ohm 5% 1/10W ±200ppm/°C Molded SMD Punched Carrier T/R")
      (fields
        (field (name "MANUFACTURER") "Panasonic")
        (field (name "TOLERANCE") "5%")
        (field (name "RESISTANCE") "10K")
        (field (name "CASE/PACKAGE") "0402")
      )
      (libsource (lib "Electronic Devices_LIB") (part "RES_10K_5%_100mW_0402"))
    )
    (comp (ref "R26")
      (value "ERJ-2GE0R00X")
      (footprint "RES_0402_RESC1005X04N")
      (description "SMD Chip Resistor, Jumper, 0 ohm, 100 mW, 0402 [1005 Metric], Thick Film, General Purpose")
      (fields
        (field (name "MANUFACTURER") "Panasonic")
        (field (name "CASE CODE (IMPERIAL)") "0402")
        (field (name "TOLERANCE") "5%")
        (field (name "RESISTANCE") "0R")
      )
      (libsource (lib "Electronic Devices_LIB") (part "RES_0R_5%_100mW_0402"))
    )
    (comp (ref "R27")
      (value "RC0402FR-07100KL")
      (footprint "RES_0402_RESC1005X04N")
      (description "SMD Chip Resistor, 100 kOhm, ± 1%, 63 mW, 0402 [1005 Metric], Thick Film, General Purpose")
      (fields
        (field (name "MANUFACTURER") "Yageo")
        (field (name "RESISTANCE") "100K")
        (field (name "TOLERANCE") "1%")
        (field (name "CASE/PACKAGE") "0402")
      )
      (libsource (lib "Electronic Devices_LIB") (part "RES_100K_1%_100mW_0402"))
    )
    (comp (ref "R28")
      (value "ERJ-2GEJ103X")
      (footprint "RES_0402_RESC1005X04N")
      (description "Res Thick Film 0402 10K Ohm 5% 1/10W ±200ppm/°C Molded SMD Punched Carrier T/R")
      (fields
        (field (name "MANUFACTURER") "Panasonic")
        (field (name "TOLERANCE") "5%")
        (field (name "RESISTANCE") "10K")
        (field (name "CASE/PACKAGE") "0402")
      )
      (libsource (lib "Electronic Devices_LIB") (part "RES_10K_5%_100mW_0402"))
    )
    (comp (ref "R29")
      (value "ERJ-2GEJ103X")
      (footprint "RES_0402_RESC1005X04N")
      (description "Res Thick Film 0402 10K Ohm 5% 1/10W ±200ppm/°C Molded SMD Punched Carrier T/R")
      (fields
        (field (name "MANUFACTURER") "Panasonic")
        (field (name "TOLERANCE") "5%")
        (field (name "RESISTANCE") "10K")
        (field (name "CASE/PACKAGE") "0402")
      )
      (libsource (lib "Electronic Devices_LIB") (part "RES_10K_5%_100mW_0402"))
    )
    (comp (ref "R30")
      (value "RC0402FR-07100KL")
      (footprint "RES_0402_RESC1005X04N")
      (description "SMD Chip Resistor, 100 kOhm, ± 1%, 63 mW, 0402 [1005 Metric], Thick Film, General Purpose")
      (fields
        (field (name "MANUFACTURER") "Yageo")
        (field (name "RESISTANCE") "100K")
        (field (name "TOLERANCE") "1%")
        (field (name "CASE/PACKAGE") "0402")
      )
      (libsource (lib "Electronic Devices_LIB") (part "RES_100K_1%_100mW_0402"))
    )
    (comp (ref "R232")
      (value "ERJ-2GE0R00X")
      (footprint "RES_0402_RESC1005X04N")
      (description "SMD Chip Resistor, Jumper, 0 ohm, 100 mW, 0402 [1005 Metric], Thick Film, General Purpose")
      (fields
        (field (name "MANUFACTURER") "Panasonic")
        (field (name "CASE CODE (IMPERIAL)") "0402")
        (field (name "TOLERANCE") "5%")
        (field (name "RESISTANCE") "0R")
      )
      (libsource (lib "Electronic Devices_LIB") (part "RES_0R_5%_100mW_0402"))
    )
    (comp (ref "R237")
      (value "ERJ-2GE0R00X")
      (footprint "RES_0402_RESC1005X04N")
      (description "SMD Chip Resistor, Jumper, 0 ohm, 100 mW, 0402 [1005 Metric], Thick Film, General Purpose")
      (fields
        (field (name "MANUFACTURER") "Panasonic")
        (field (name "CASE CODE (IMPERIAL)") "0402")
        (field (name "TOLERANCE") "5%")
        (field (name "RESISTANCE") "0R")
      )
      (libsource (lib "Electronic Devices_LIB") (part "RES_0R_5%_100mW_0402"))
    )
    (comp (ref "TP1")
      (value "NO COMPONENT")
      (footprint "TP_PAD_0.5MM_SMD_ROUND")
      (description "Test Point, SMD pad, round, 1.5mm, 1.6mm, 3mm diameter")
      (libsource (lib "Electronic Devices_LIB") (part "TP_PAD_SMD_SMALL"))
    )
    (comp (ref "TP2")
      (value "NO COMPONENT")
      (footprint "TP_PAD_0.5MM_SMD_ROUND")
      (description "Test Point, SMD pad, round, 1.5mm, 1.6mm, 3mm diameter")
      (libsource (lib "Electronic Devices_LIB") (part "TP_PAD_SMD_SMALL"))
    )
    (comp (ref "TP3")
      (value "NO COMPONENT")
      (footprint "TP_PAD_0.5MM_SMD_ROUND")
      (description "Test Point, SMD pad, round, 1.5mm, 1.6mm, 3mm diameter")
      (libsource (lib "Electronic Devices_LIB") (part "TP_PAD_SMD_SMALL"))
    )
    (comp (ref "TP4")
      (value "NO COMPONENT")
      (footprint "TP_PAD_0.5MM_SMD_ROUND")
      (description "Test Point, SMD pad, round, 1.5mm, 1.6mm, 3mm diameter")
      (libsource (lib "Electronic Devices_LIB") (part "TP_PAD_SMD_SMALL"))
    )
    (comp (ref "TP5")
      (value "NO COMPONENT")
      (footprint "TP_PAD_0.5MM_SMD_ROUND")
      (description "Test Point, SMD pad, round, 1.5mm, 1.6mm, 3mm diameter")
      (libsource (lib "Electronic Devices_LIB") (part "TP_PAD_SMD_SMALL"))
    )
    (comp (ref "TP6")
      (value "NO COMPONENT")
      (footprint "TP_PAD_0.5MM_SMD_ROUND")
      (description "Test Point, SMD pad, round, 1.5mm, 1.6mm, 3mm diameter")
      (libsource (lib "Electronic Devices_LIB") (part "TP_PAD_SMD_SMALL"))
    )
    (comp (ref "TP7")
      (value "NO COMPONENT")
      (footprint "TP_PAD_0.5MM_SMD_ROUND")
      (description "Test Point, SMD pad, round, 1.5mm, 1.6mm, 3mm diameter")
      (libsource (lib "Electronic Devices_LIB") (part "TP_PAD_SMD_SMALL"))
    )
    (comp (ref "TP8")
      (value "NO COMPONENT")
      (footprint "TP_PAD_0.5MM_SMD_ROUND")
      (description "Test Point, SMD pad, round, 1.5mm, 1.6mm, 3mm diameter")
      (libsource (lib "Electronic Devices_LIB") (part "TP_PAD_SMD_SMALL"))
    )
    (comp (ref "TP9")
      (value "NO COMPONENT")
      (footprint "TP_PAD_0.5MM_SMD_ROUND")
      (description "Test Point, SMD pad, round, 1.5mm, 1.6mm, 3mm diameter")
      (libsource (lib "Electronic Devices_LIB") (part "TP_PAD_SMD_SMALL"))
    )
    (comp (ref "TP10")
      (value "NO COMPONENT")
      (footprint "TP_PAD_0.5MM_SMD_ROUND")
      (description "Test Point, SMD pad, round, 1.5mm, 1.6mm, 3mm diameter")
      (libsource (lib "Electronic Devices_LIB") (part "TP_PAD_SMD_SMALL"))
    )
    (comp (ref "TP11")
      (value "NO COMPONENT")
      (footprint "TP_PAD_0.5MM_SMD_ROUND")
      (description "Test Point, SMD pad, round, 1.5mm, 1.6mm, 3mm diameter")
      (libsource (lib "Electronic Devices_LIB") (part "TP_PAD_SMD_SMALL"))
    )
    (comp (ref "TP12")
      (value "NO COMPONENT")
      (footprint "TP_PAD_0.5MM_SMD_ROUND")
      (description "Test Point, SMD pad, round, 1.5mm, 1.6mm, 3mm diameter")
      (libsource (lib "Electronic Devices_LIB") (part "TP_PAD_SMD_SMALL"))
    )
    (comp (ref "TP13")
      (value "NO COMPONENT")
      (footprint "TP_PAD_0.5MM_SMD_ROUND")
      (description "Test Point, SMD pad, round, 1.5mm, 1.6mm, 3mm diameter")
      (libsource (lib "Electronic Devices_LIB") (part "TP_PAD_SMD_SMALL"))
    )
    (comp (ref "TP14")
      (value "NO COMPONENT")
      (footprint "TP_PAD_0.5MM_SMD_ROUND")
      (description "Test Point, SMD pad, round, 1.5mm, 1.6mm, 3mm diameter")
      (libsource (lib "Electronic Devices_LIB") (part "TP_PAD_SMD_SMALL"))
    )
    (comp (ref "TP15")
      (value "NO COMPONENT")
      (footprint "TP_PAD_0.5MM_SMD_ROUND")
      (description "Test Point, SMD pad, round, 1.5mm, 1.6mm, 3mm diameter")
      (libsource (lib "Electronic Devices_LIB") (part "TP_PAD_SMD_SMALL"))
    )
    (comp (ref "TP16")
      (value "NO COMPONENT")
      (footprint "TP_PAD_0.5MM_SMD_ROUND")
      (description "Test Point, SMD pad, round, 1.5mm, 1.6mm, 3mm diameter")
      (libsource (lib "Electronic Devices_LIB") (part "TP_PAD_SMD_SMALL"))
    )
    (comp (ref "TP17")
      (value "NO COMPONENT")
      (footprint "TP_PAD_0.5MM_SMD_ROUND")
      (description "Test Point, SMD pad, round, 1.5mm, 1.6mm, 3mm diameter")
      (libsource (lib "Electronic Devices_LIB") (part "TP_PAD_SMD_SMALL"))
    )
    (comp (ref "TP55")
      (value "NO COMPONENT")
      (footprint "TP_PAD_0.5MM_SMD_ROUND")
      (description "Test Point, SMD pad, round, 1.5mm, 1.6mm, 3mm diameter")
      (libsource (lib "Electronic Devices_LIB") (part "TP_PAD_SMD_SMALL"))
    )
    (comp (ref "U2")
      (value "MPF7100BVMA1ES")
      (footprint "HVQFN48_SOT619-27D_NXP")
      (description "PMIC, i.MX8, 5 buck, 2 LDO RoHS Compliant: Yes")
      (fields (field (name "MANUFACTURER") "NXP Semiconductors"))
      (libsource (lib "Electronic Devices_LIB") (part "IC_PMIC_IMX8_MPF7100BVMA1ES"))
    )
  )
  (nets
    (net (code "3") (name "/PMIC_FSOB") (class "Default")
      (node (ref "R20") (pin "2") (pinfunction "2_2") (pintype "passive"))
      (node (ref "U2") (pin "36") (pinfunction "FSOB_36") (pintype "passive"))
    )
    (net (code "4") (name "/PMIC_I2C_SCL") (class "Default")
      (node (ref "U2") (pin "11") (pinfunction "SCL_11") (pintype "passive"))
    )
    (net (code "5") (name "/PMIC_I2C_SDA") (class "Default")
      (node (ref "U2") (pin "10") (pinfunction "SDA_10") (pintype "passive"))
    )
    (net (code "6") (name "/PMIC_INT_B") (class "Default")
      (node (ref "R18") (pin "1") (pinfunction "1_1") (pintype "passive"))
    )
    (net (code "7") (name "/PMIC_LDO2_EN") (class "Default")
      (node (ref "R10") (pin "1") (pinfunction "1_1") (pintype "passive"))
      (node (ref "R12") (pin "1") (pinfunction "1_1") (pintype "passive"))
      (node (ref "R14") (pin "2") (pinfunction "2_2") (pintype "passive"))
    )
    (net (code "8") (name "/PMIC_ON_REQ") (class "Default")
      (node (ref "R17") (pin "1") (pinfunction "1_1") (pintype "passive"))
    )
    (net (code "9") (name "/PMIC_PG") (class "Default")
      (node (ref "R23") (pin "1") (pinfunction "1_1") (pintype "passive"))
      (node (ref "TP13") (pin "1") (pinfunction "1_1") (pintype "passive"))
      (node (ref "U2") (pin "38") (pinfunction "PGOOD_38") (pintype "passive"))
    )
    (net (code "10") (name "/PMIC_RESETBMCU") (class "Default")
      (node (ref "R24") (pin "2") (pinfunction "2_2") (pintype "passive"))
      (node (ref "R26") (pin "2") (pinfunction "2_2") (pintype "passive"))
      (node (ref "TP55") (pin "1") (pinfunction "1_1") (pintype "passive"))
    )
    (net (code "11") (name "/PMIC_STBY") (class "Default")
      (node (ref "R15") (pin "1") (pinfunction "1_1") (pintype "passive"))
    )
    (net (code "12") (name "/PMIC_WDOG_IN") (class "Default")
      (node (ref "R19") (pin "1") (pinfunction "1_1") (pintype "passive"))
    )
    (net (code "13") (name "/SD1_VSELECT") (class "Default")
      (node (ref "R11") (pin "1") (pinfunction "1_1") (pintype "passive"))
      (node (ref "R13") (pin "2") (pinfunction "2_2") (pintype "passive"))
      (node (ref "R9") (pin "1") (pinfunction "1_1") (pintype "passive"))
    )
    (net (code "14") (name "/SW1FB") (class "Default")
      (node (ref "R4") (pin "1") (pinfunction "1_1") (pintype "passive"))
      (node (ref "U2") (pin "31") (pinfunction "SW1FB_31") (pintype "passive"))
    )
    (net (code "15") (name "/SW1LX") (class "Default")
      (node (ref "L1") (pin "1") (pinfunction "1_1") (pintype "passive"))
      (node (ref "U2") (pin "40") (pinfunction "SW1LX_40") (pintype "passive"))
    )
    (net (code "16") (name "/SW2FB") (class "Default")
      (node (ref "R5") (pin "1") (pinfunction "1_1") (pintype "passive"))
      (node (ref "U2") (pin "30") (pinfunction "SW2FB_30") (pintype "passive"))
    )
    (net (code "17") (name "/SW2LX") (class "Default")
      (node (ref "L2") (pin "1") (pinfunction "1_1") (pintype "passive"))
      (node (ref "U2") (pin "41") (pinfunction "SW2LX_41") (pintype "passive"))
    )
    (net (code "18") (name "/SW3FB") (class "Default")
      (node (ref "R6") (pin "1") (pinfunction "1_1") (pintype "passive"))
      (node (ref "U2") (pin "7") (pinfunction "SW3FB_7") (pintype "passive"))
    )
    (net (code "19") (name "/SW3LX") (class "Default")
      (node (ref "L3") (pin "1") (pinfunction "1_1") (pintype "passive"))
      (node (ref "U2") (pin "44") (pinfunction "SW3LX_44") (pintype "passive"))
    )
    (net (code "20") (name "/SW4FB") (class "Default")
      (node (ref "R7") (pin "1") (pinfunction "1_1") (pintype "passive"))
      (node (ref "U2") (pin "6") (pinfunction "SW4FB_6") (pintype "passive"))
    )
    (net (code "21") (name "/SW4LX") (class "Default")
      (node (ref "L4") (pin "1") (pinfunction "1_1") (pintype "passive"))
      (node (ref "U2") (pin "45") (pinfunction "SW4LX_45") (pintype "passive"))
    )
    (net (code "22") (name "/SW5FB") (class "Default")
      (node (ref "R8") (pin "1") (pinfunction "1_1") (pintype "passive"))
      (node (ref "U2") (pin "12") (pinfunction "SW5FB_12") (pintype "passive"))
    )
    (net (code "23") (name "/SW5LX") (class "Default")
      (node (ref "L5") (pin "1") (pinfunction "1_1") (pintype "passive"))
      (node (ref "U2") (pin "16") (pinfunction "SW5LX_16") (pintype "passive"))
    )
    (net (code "26") (name "1V8") (class "Default")
      (node (ref "R237") (pin "2") (pinfunction "2_2") (pintype "passive"))
    )
    (net (code "27") (name "3V3_PMIC") (class "Default")
      (node (ref "C39") (pin "2") (pinfunction "2_2") (pintype "passive"))
      (node (ref "C40") (pin "2") (pinfunction "2_2") (pintype "passive"))
      (node (ref "C41") (pin "2") (pinfunction "2_2") (pintype "passive"))
      (node (ref "C42") (pin "2") (pinfunction "2_2") (pintype "passive"))
      (node (ref "C43") (pin "2") (pinfunction "2_2") (pintype "passive"))
      (node (ref "C44") (pin "2") (pinfunction "2_2") (pintype "passive"))
      (node (ref "C46") (pin "2") (pinfunction "2_2") (pintype "passive"))
      (node (ref "R232") (pin "2") (pinfunction "2_2") (pintype "passive"))
      (node (ref "U2") (pin "15") (pinfunction "SW5IN_15") (pintype "passive"))
      (node (ref "U2") (pin "20") (pinfunction "LDO1IN_20") (pintype "passive"))
      (node (ref "U2") (pin "27") (pinfunction "VIN_27") (pintype "passive"))
      (node (ref "U2") (pin "39") (pinfunction "SW1IN_39") (pintype "passive"))
      (node (ref "U2") (pin "42") (pinfunction "SW2IN_42") (pintype "passive"))
      (node (ref "U2") (pin "43") (pinfunction "SW3IN_43") (pintype "passive"))
      (node (ref "U2") (pin "46") (pinfunction "SW4IN_46") (pintype "passive"))
    )
    (net (code "28") (name "3V3_PS") (class "Default")
      (node (ref "R232") (pin "1") (pinfunction "1_1") (pintype "passive"))
    )
    (net (code "29") (name "5V0_PS") (class "Default")
      (node (ref "C45") (pin "2") (pinfunction "2_2") (pintype "passive"))
      (node (ref "U2") (pin "19") (pinfunction "LDO2IN_19") (pintype "passive"))
    )
    (net (code "30") (name "GND") (class "Default")
      (node (ref "C39") (pin "1") (pinfunction "1_1") (pintype "passive"))
      (node (ref "C40") (pin "1") (pinfunction "1_1") (pintype "passive"))
      (node (ref "C41") (pin "1") (pinfunction "1_1") (pintype "passive"))
      (node (ref "C42") (pin "1") (pinfunction "1_1") (pintype "passive"))
      (node (ref "C43") (pin "1") (pinfunction "1_1") (pintype "passive"))
      (node (ref "C44") (pin "1") (pinfunction "1_1") (pintype "passive"))
      (node (ref "C45") (pin "1") (pinfunction "1_1") (pintype "passive"))
      (node (ref "C46") (pin "1") (pinfunction "1_1") (pintype "passive"))
      (node (ref "C47") (pin "1") (pinfunction "1_1") (pintype "passive"))
      (node (ref "C48") (pin "1") (pinfunction "1_1") (pintype "passive"))
      (node (ref "C49") (pin "1") (pinfunction "1_1") (pintype "passive"))
      (node (ref "C50") (pin "1") (pinfunction "1_1") (pintype "passive"))
      (node (ref "C51") (pin "1") (pinfunction "1_1") (pintype "passive"))
      (node (ref "C52") (pin "1") (pinfunction "1_1") (pintype "passive"))
      (node (ref "C53") (pin "1") (pinfunction "1_1") (pintype "passive"))
      (node (ref "C54") (pin "1") (pinfunction "1_1") (pintype "passive"))
      (node (ref "C55") (pin "1") (pinfunction "1_1") (pintype "passive"))
      (node (ref "C56") (pin "1") (pinfunction "1_1") (pintype "passive"))
      (node (ref "C57") (pin "1") (pinfunction "1_1") (pintype "passive"))
      (node (ref "C58") (pin "1") (pinfunction "1_1") (pintype "passive"))
      (node (ref "C59") (pin "1") (pinfunction "1_1") (pintype "passive"))
      (node (ref "C60") (pin "1") (pinfunction "1_1") (pintype "passive"))
      (node (ref "C61") (pin "1") (pinfunction "1_1") (pintype "passive"))
      (node (ref "C62") (pin "1") (pinfunction "1_1") (pintype "passive"))
      (node (ref "C63") (pin "1") (pinfunction "1_1") (pintype "passive"))
      (node (ref "C64") (pin "1") (pinfunction "1_1") (pintype "passive"))
      (node (ref "C65") (pin "1") (pinfunction "1_1") (pintype "passive"))
      (node (ref "C66") (pin "1") (pinfunction "1_1") (pintype "passive"))
      (node (ref "C67") (pin "1") (pinfunction "1_1") (pintype "passive"))
      (node (ref "C68") (pin "1") (pinfunction "1_1") (pintype "passive"))
      (node (ref "C69") (pin "1") (pinfunction "1_1") (pintype "passive"))
      (node (ref "C70") (pin "1") (pinfunction "1_1") (pintype "passive"))
      (node (ref "C71") (pin "1") (pinfunction "1_1") (pintype "passive"))
      (node (ref "C72") (pin "1") (pinfunction "1_1") (pintype "passive"))
      (node (ref "C73") (pin "1") (pinfunction "1_1") (pintype "passive"))
      (node (ref "R13") (pin "1") (pinfunction "1_1") (pintype "passive"))
      (node (ref "R14") (pin "1") (pinfunction "1_1") (pintype "passive"))
      (node (ref "R27") (pin "1") (pinfunction "1_1") (pintype "passive"))
      (node (ref "R28") (pin "1") (pinfunction "1_1") (pintype "passive"))
      (node (ref "R29") (pin "1") (pinfunction "1_1") (pintype "passive"))
      (node (ref "R30") (pin "1") (pinfunction "1_1") (pintype "passive"))
      (node (ref "U2") (pin "26") (pinfunction "AGND_26") (pintype "passive"))
      (node (ref "U2") (pin "29") (pinfunction "DGND_29") (pintype "passive"))
      (node (ref "U2") (pin "49") (pinfunction "EPAD_49") (pintype "passive"))
    )
    (net (code "31") (name "Net-(U2-AMUX)") (class "Default")
      (node (ref "TP15") (pin "1") (pinfunction "1_1") (pintype "passive"))
      (node (ref "U2") (pin "25") (pinfunction "AMUX_25") (pintype "passive"))
    )
    (net (code "32") (name "Net-(U2-EWARN)") (class "Default")
      (node (ref "R27") (pin "2") (pinfunction "2_2") (pintype "passive"))
      (node (ref "TP17") (pin "1") (pinfunction "1_1") (pintype "passive"))
      (node (ref "U2") (pin "3") (pinfunction "EWARN_3") (pintype "passive"))
    )
    (net (code "33") (name "Net-(U2-INTB)") (class "Default")
      (node (ref "R18") (pin "2") (pinfunction "2_2") (pintype "passive"))
      (node (ref "U2") (pin "37") (pinfunction "INTB_37") (pintype "passive"))
    )
    (net (code "34") (name "Net-(U2-LDO2EN)") (class "Default")
      (node (ref "R12") (pin "2") (pinfunction "2_2") (pintype "passive"))
      (node (ref "U2") (pin "4") (pinfunction "LDO2EN_4") (pintype "passive"))
    )
    (net (code "35") (name "Net-(U2-PWRON)") (class "Default")
      (node (ref "R17") (pin "2") (pinfunction "2_2") (pintype "passive"))
      (node (ref "U2") (pin "34") (pinfunction "PWRON_34") (pintype "passive"))
    )
    (net (code "36") (name "Net-(U2-RESETBMCU)") (class "Default")
      (node (ref "R26") (pin "1") (pinfunction "1_1") (pintype "passive"))
      (node (ref "U2") (pin "35") (pinfunction "RESETBMCU_35") (pintype "passive"))
    )
    (net (code "37") (name "Net-(U2-STANDBY)") (class "Default")
      (node (ref "R15") (pin "2") (pinfunction "2_2") (pintype "passive"))
      (node (ref "U2") (pin "33") (pinfunction "STANDBY_33") (pintype "passive"))
    )
    (net (code "38") (name "Net-(U2-SYNCIN)") (class "Default")
      (node (ref "R30") (pin "2") (pinfunction "2_2") (pintype "passive"))
      (node (ref "TP16") (pin "1") (pinfunction "1_1") (pintype "passive"))
      (node (ref "U2") (pin "5") (pinfunction "SYNCIN_5") (pintype "passive"))
    )
    (net (code "39") (name "Net-(U2-SYNCOUT)") (class "Default")
      (node (ref "TP14") (pin "1") (pinfunction "1_1") (pintype "passive"))
      (node (ref "U2") (pin "2") (pinfunction "SYNCOUT_2") (pintype "passive"))
    )
    (net (code "40") (name "Net-(U2-TBBEN)") (class "Default")
      (node (ref "R22") (pin "1") (pinfunction "1_1") (pintype "passive"))
      (node (ref "R29") (pin "2") (pinfunction "2_2") (pintype "passive"))
      (node (ref "U2") (pin "32") (pinfunction "TBBEN_32") (pintype "passive"))
    )
    (net (code "41") (name "Net-(U2-VDDOTP)") (class "Default")
      (node (ref "R21") (pin "1") (pinfunction "1_1") (pintype "passive"))
      (node (ref "R28") (pin "2") (pinfunction "2_2") (pintype "passive"))
      (node (ref "U2") (pin "8") (pinfunction "VDDOTP_8") (pintype "passive"))
    )
    (net (code "42") (name "Net-(U2-VSELECT)") (class "Default")
      (node (ref "R11") (pin "2") (pinfunction "2_2") (pintype "passive"))
      (node (ref "U2") (pin "48") (pinfunction "VSELECT_48") (pintype "passive"))
    )
    (net (code "43") (name "Net-(U2-VSNVS2)") (class "Default")
      (node (ref "R16") (pin "1") (pinfunction "1_1") (pintype "passive"))
      (node (ref "TP9") (pin "1") (pinfunction "1_1") (pintype "passive"))
      (node (ref "U2") (pin "22") (pinfunction "VSNVS2_22") (pintype "passive"))
    )
    (net (code "44") (name "Net-(U2-WDI)") (class "Default")
      (node (ref "R19") (pin "2") (pinfunction "2_2") (pintype "passive"))
      (node (ref "U2") (pin "1") (pinfunction "WDI_1") (pintype "passive"))
    )
    (net (code "45") (name "Net-(U2-XFAILB)") (class "Default")
      (node (ref "R25") (pin "1") (pinfunction "1_1") (pintype "passive"))
      (node (ref "U2") (pin "17") (pinfunction "XFAILB_17") (pintype "passive"))
    )
    (net (code "46") (name "PMIC_VDD_1V8") (class "Default")
      (node (ref "C47") (pin "2") (pinfunction "2_2") (pintype "passive"))
      (node (ref "C70") (pin "2") (pinfunction "2_2") (pintype "passive"))
      (node (ref "C71") (pin "2") (pinfunction "2_2") (pintype "passive"))
      (node (ref "C72") (pin "2") (pinfunction "2_2") (pintype "passive"))
      (node (ref "C73") (pin "2") (pinfunction "2_2") (pintype "passive"))
      (node (ref "L5") (pin "2") (pinfunction "2_2") (pintype "passive"))
      (node (ref "R10") (pin "2") (pinfunction "2_2") (pintype "passive"))
      (node (ref "R20") (pin "1") (pinfunction "1_1") (pintype "passive"))
      (node (ref "R23") (pin "2") (pinfunction "2_2") (pintype "passive"))
      (node (ref "R237") (pin "1") (pinfunction "1_1") (pintype "passive"))
      (node (ref "R24") (pin "1") (pinfunction "1_1") (pintype "passive"))
      (node (ref "R8") (pin "2") (pinfunction "2_2") (pintype "passive"))
      (node (ref "R9") (pin "2") (pinfunction "2_2") (pintype "passive"))
      (node (ref "TP5") (pin "1") (pinfunction "1_1") (pintype "passive"))
      (node (ref "U2") (pin "9") (pinfunction "VDDIO_9") (pintype "passive"))
    )
    (net (code "47") (name "PMIC_VDD_ANA") (class "Default")
      (node (ref "C48") (pin "2") (pinfunction "2_2") (pintype "passive"))
      (node (ref "TP6") (pin "1") (pinfunction "1_1") (pintype "passive"))
      (node (ref "U2") (pin "21") (pinfunction "LDO1OUT_21") (pintype "passive"))
    )
    (net (code "48") (name "PMIC_VDD_DDRIO") (class "Default")
      (node (ref "C66") (pin "2") (pinfunction "2_2") (pintype "passive"))
      (node (ref "C67") (pin "2") (pinfunction "2_2") (pintype "passive"))
      (node (ref "C68") (pin "2") (pinfunction "2_2") (pintype "passive"))
      (node (ref "C69") (pin "2") (pinfunction "2_2") (pintype "passive"))
      (node (ref "L4") (pin "2") (pinfunction "2_2") (pintype "passive"))
      (node (ref "R7") (pin "2") (pinfunction "2_2") (pintype "passive"))
      (node (ref "TP4") (pin "1") (pinfunction "1_1") (pintype "passive"))
    )
    (net (code "49") (name "PMIC_VDD_MAIN") (class "Default")
      (node (ref "C54") (pin "2") (pinfunction "2_2") (pintype "passive"))
      (node (ref "C55") (pin "2") (pinfunction "2_2") (pintype "passive"))
      (node (ref "C56") (pin "2") (pinfunction "2_2") (pintype "passive"))
      (node (ref "C57") (pin "2") (pinfunction "2_2") (pintype "passive"))
      (node (ref "L1") (pin "2") (pinfunction "2_2") (pintype "passive"))
      (node (ref "R4") (pin "2") (pinfunction "2_2") (pintype "passive"))
      (node (ref "TP1") (pin "1") (pinfunction "1_1") (pintype "passive"))
    )
    (net (code "50") (name "PMIC_VDD_MEMC") (class "Default")
      (node (ref "C58") (pin "2") (pinfunction "2_2") (pintype "passive"))
      (node (ref "C59") (pin "2") (pinfunction "2_2") (pintype "passive"))
      (node (ref "C60") (pin "2") (pinfunction "2_2") (pintype "passive"))
      (node (ref "C61") (pin "2") (pinfunction "2_2") (pintype "passive"))
      (node (ref "L2") (pin "2") (pinfunction "2_2") (pintype "passive"))
      (node (ref "R5") (pin "2") (pinfunction "2_2") (pintype "passive"))
      (node (ref "TP2") (pin "1") (pinfunction "1_1") (pintype "passive"))
    )
    (net (code "51") (name "PMIC_VDD_SD") (class "Default")
      (node (ref "C49") (pin "2") (pinfunction "2_2") (pintype "passive"))
      (node (ref "TP7") (pin "1") (pinfunction "1_1") (pintype "passive"))
      (node (ref "U2") (pin "18") (pinfunction "LDO2OUT_18") (pintype "passive"))
    )
    (net (code "52") (name "PMIC_VDD_SNVS1") (class "Default")
      (node (ref "C51") (pin "2") (pinfunction "2_2") (pintype "passive"))
      (node (ref "TP8") (pin "1") (pinfunction "1_1") (pintype "passive"))
      (node (ref "U2") (pin "23") (pinfunction "VSNVS1_23") (pintype "passive"))
    )
    (net (code "53") (name "PMIC_VDD_SNVS2") (class "Default")
      (node (ref "C50") (pin "2") (pinfunction "2_2") (pintype "passive"))
      (node (ref "R16") (pin "2") (pinfunction "2_2") (pintype "passive"))
      (node (ref "TP10") (pin "1") (pinfunction "1_1") (pintype "passive"))
    )
    (net (code "54") (name "PMIC_VDD_V2X_VTT") (class "Default")
      (node (ref "C62") (pin "2") (pinfunction "2_2") (pintype "passive"))
      (node (ref "C63") (pin "2") (pinfunction "2_2") (pintype "passive"))
      (node (ref "C64") (pin "2") (pinfunction "2_2") (pintype "passive"))
      (node (ref "C65") (pin "2") (pinfunction "2_2") (pintype "passive"))
      (node (ref "L3") (pin "2") (pinfunction "2_2") (pintype "passive"))
      (node (ref "R6") (pin "2") (pinfunction "2_2") (pintype "passive"))
      (node (ref "TP3") (pin "1") (pinfunction "1_1") (pintype "passive"))
    )
    (net (code "55") (name "V1P5A_1V5") (class "Default")
      (node (ref "C52") (pin "2") (pinfunction "2_2") (pintype "passive"))
      (node (ref "R25") (pin "2") (pinfunction "2_2") (pintype "passive"))
      (node (ref "TP11") (pin "1") (pinfunction "1_1") (pintype "passive"))
      (node (ref "U2") (pin "24") (pinfunction "V1P5A_24") (pintype "passive"))
    )
    (net (code "56") (name "V1P5D_1V5") (class "Default")
      (node (ref "C53") (pin "2") (pinfunction "2_2") (pintype "passive"))
      (node (ref "R21") (pin "2") (pinfunction "2_2") (pintype "passive"))
      (node (ref "R22") (pin "2") (pinfunction "2_2") (pintype "passive"))
      (node (ref "TP12") (pin "1") (pinfunction "1_1") (pintype "passive"))
      (node (ref "U2") (pin "28") (pinfunction "V1P5D_28") (pintype "passive"))
    )
    (net (code "57") (name "unconnected-(U2-NC-Pad47)") (class "Default")
      (node (ref "U2") (pin "47") (pinfunction "NC_47") (pintype "passive+no_connect"))
    )
    (net (code "58") (name "unconnected-(U2-NC1-Pad14)") (class "Default")
      (node (ref "U2") (pin "14") (pinfunction "NC1_14") (pintype "passive+no_connect"))
    )
    (net (code "59") (name "unconnected-(U2-XINTB-Pad13)") (class "Default")
      (node (ref "U2") (pin "13") (pinfunction "XINTB_13") (pintype "passive+no_connect"))
    )
  )
)
